# Teensy-Maxuino-Slave-A4988-stepper.net
KiCad netlist of a schematic drawn in EAGLE
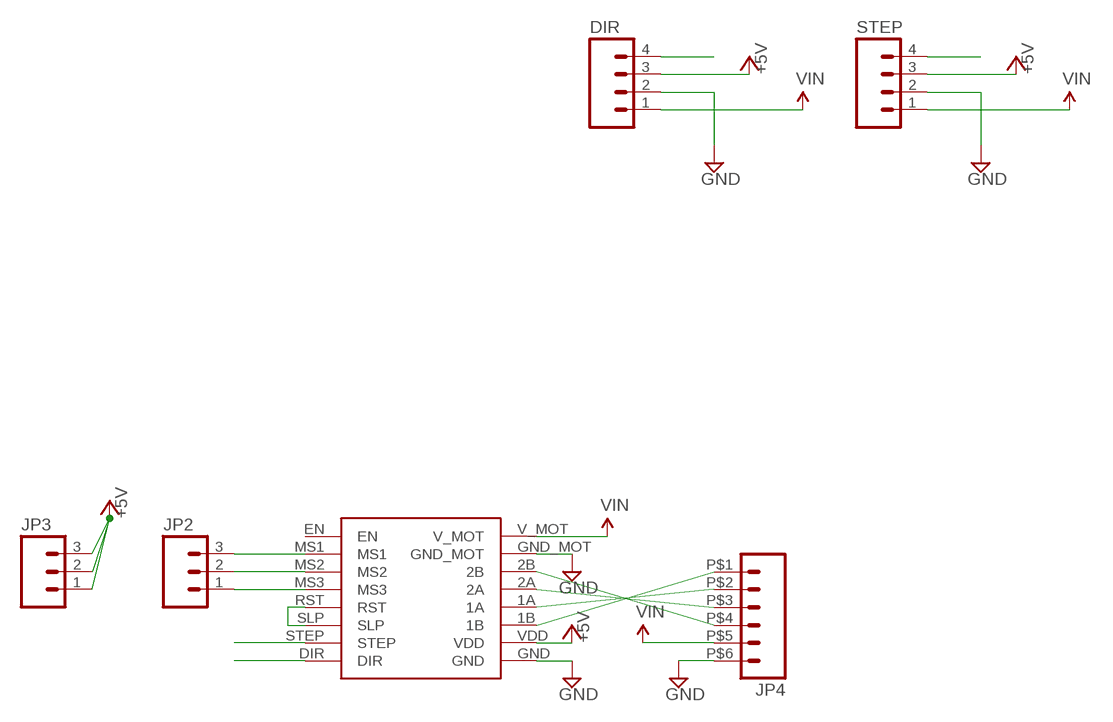
[diagram p0: schematic, sheet 1]

(export (version "E")
  (design (tool "Eeschema 10.0.6"))
  (components
    (comp (ref "DIR")
      (value "M04PTH")
      (footprint "eagle-import:1X04")
      (libsource (lib "eagle-import") (part "M04PTH"))
    )
    (comp (ref "JP2")
      (value "M03PTH")
      (footprint "eagle-import:1X03")
      (libsource (lib "eagle-import") (part "M03PTH"))
    )
    (comp (ref "JP3")
      (value "M03PTH")
      (footprint "eagle-import:1X03")
      (libsource (lib "eagle-import") (part "M03PTH"))
    )
    (comp (ref "JP4")
      (value "M06")
      (footprint "eagle-import:SPRINGTERMINAL-2.54MM-6")
      (libsource (lib "eagle-import") (part "M06"))
    )
    (comp (ref "STEP")
      (value "M04PTH")
      (footprint "eagle-import:1X04")
      (libsource (lib "eagle-import") (part "M04PTH"))
    )
    (comp (ref "U$1")
      (value "POLOLU_A4988")
      (footprint "eagle-import:POLOLU_A4988")
      (libsource (lib "eagle-import") (part "POLOLU_A4988"))
    )
  )
  (nets
    (net (code "1") (name "+5V") (class "Default")
      (node (ref "DIR") (pin "3") (pinfunction "3_3") (pintype "passive"))
      (node (ref "JP3") (pin "1") (pinfunction "1_1") (pintype "passive"))
      (node (ref "JP3") (pin "2") (pinfunction "2_2") (pintype "passive"))
      (node (ref "JP3") (pin "3") (pinfunction "3_3") (pintype "passive"))
      (node (ref "STEP") (pin "3") (pinfunction "3_3") (pintype "passive"))
      (node (ref "U$1") (pin "VDD") (pinfunction "VDD_VDD") (pintype "bidirectional"))
    )
    (net (code "2") (name "/DIR") (class "Default")
      (node (ref "DIR") (pin "4") (pinfunction "4_4") (pintype "passive"))
      (node (ref "U$1") (pin "DIR") (pinfunction "DIR_DIR") (pintype "bidirectional"))
    )
    (net (code "3") (name "/STEP") (class "Default")
      (node (ref "STEP") (pin "4") (pinfunction "4_4") (pintype "passive"))
      (node (ref "U$1") (pin "STEP") (pinfunction "STEP_STEP") (pintype "bidirectional"))
    )
    (net (code "4") (name "GND") (class "Default")
      (node (ref "DIR") (pin "2") (pinfunction "2_2") (pintype "passive"))
      (node (ref "JP4") (pin "P$6") (pinfunction "6_P$6") (pintype "passive"))
      (node (ref "STEP") (pin "2") (pinfunction "2_2") (pintype "passive"))
      (node (ref "U$1") (pin "GND") (pinfunction "GND_GND") (pintype "bidirectional"))
      (node (ref "U$1") (pin "GND_MOT") (pinfunction "GND_MOT_GND_MOT") (pintype "bidirectional"))
    )
    (net (code "5") (name "Net-(JP2-Pad1)") (class "Default")
      (node (ref "JP2") (pin "1") (pinfunction "1_1") (pintype "passive"))
      (node (ref "U$1") (pin "MS3") (pinfunction "MS3_MS3") (pintype "bidirectional"))
    )
    (net (code "6") (name "Net-(JP2-Pad2)") (class "Default")
      (node (ref "JP2") (pin "2") (pinfunction "2_2") (pintype "passive"))
      (node (ref "U$1") (pin "MS2") (pinfunction "MS2_MS2") (pintype "bidirectional"))
    )
    (net (code "7") (name "Net-(JP2-Pad3)") (class "Default")
      (node (ref "JP2") (pin "3") (pinfunction "3_3") (pintype "passive"))
      (node (ref "U$1") (pin "MS1") (pinfunction "MS1_MS1") (pintype "bidirectional"))
    )
    (net (code "8") (name "Net-(JP4-1)") (class "Default")
      (node (ref "JP4") (pin "P$1") (pinfunction "1_P$1") (pintype "passive"))
      (node (ref "U$1") (pin "1B") (pinfunction "1B_1B") (pintype "bidirectional"))
    )
    (net (code "9") (name "Net-(JP4-2)") (class "Default")
      (node (ref "JP4") (pin "P$2") (pinfunction "2_P$2") (pintype "passive"))
      (node (ref "U$1") (pin "1A") (pinfunction "1A_1A") (pintype "bidirectional"))
    )
    (net (code "10") (name "Net-(JP4-3)") (class "Default")
      (node (ref "JP4") (pin "P$3") (pinfunction "3_P$3") (pintype "passive"))
      (node (ref "U$1") (pin "2A") (pinfunction "2A_2A") (pintype "bidirectional"))
    )
    (net (code "11") (name "Net-(JP4-4)") (class "Default")
      (node (ref "JP4") (pin "P$4") (pinfunction "4_P$4") (pintype "passive"))
      (node (ref "U$1") (pin "2B") (pinfunction "2B_2B") (pintype "bidirectional"))
    )
    (net (code "12") (name "Net-(U$1-PadRST)") (class "Default")
      (node (ref "U$1") (pin "RST") (pinfunction "RST_RST") (pintype "bidirectional"))
      (node (ref "U$1") (pin "SLP") (pinfunction "SLP_SLP") (pintype "bidirectional"))
    )
    (net (code "13") (name "VIN") (class "Default")
      (node (ref "DIR") (pin "1") (pinfunction "1_1") (pintype "passive"))
      (node (ref "JP4") (pin "P$5") (pinfunction "5_P$5") (pintype "passive"))
      (node (ref "STEP") (pin "1") (pinfunction "1_1") (pintype "passive"))
      (node (ref "U$1") (pin "V_MOT") (pinfunction "V_MOT_V_MOT") (pintype "bidirectional"))
    )
    (net (code "14") (name "unconnected-(U$1-PadEN)") (class "Default")
      (node (ref "U$1") (pin "EN") (pinfunction "EN_EN") (pintype "bidirectional"))
    )
  )
)
